# USB_Interface.net
KiCad netlist of a schematic drawn in Altium Designer
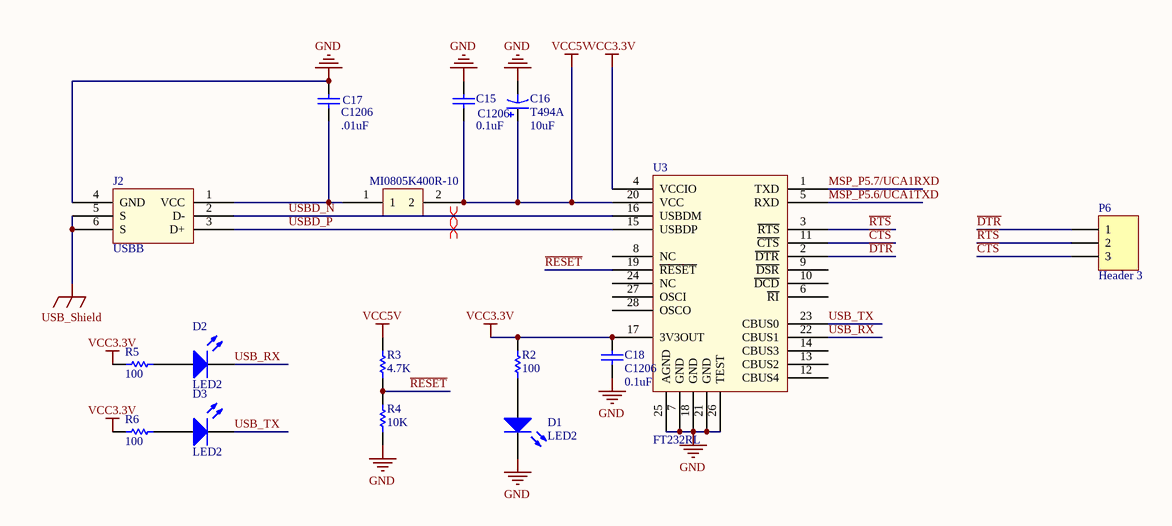
[diagram p0: USB Interface.SchDoc]

(export (version "E")
  (design (tool "Eeschema 10.0.6"))
  (components
    (comp (ref "C15")
      (value "C1206")
      (footprint "1206")
      (description "Ceramic Chip Capacitor - Standard")
      (fields (field (name "ALTIUM_VALUE") "0.1uF") (field (name "PUBLISHER") "Altium Limited"))
      (libsource (lib "KEMET Chip Capacitor") (part "C1206"))
    )
    (comp (ref "C16")
      (value "T494A")
      (footprint "A")
      (description "Solid Tantalum Chip Capacitor, Standard T494 Series - Low ESR, Industrial Grade")
      (fields (field (name "ALTIUM_VALUE") "10uF") (field (name "PUBLISHER") "Altium Limited"))
      (libsource (lib "KEMET Chip Capacitor") (part "T494A"))
    )
    (comp (ref "C17")
      (value "C1206")
      (footprint "1206")
      (description "Ceramic Chip Capacitor - Standard")
      (fields (field (name "ALTIUM_VALUE") ".01uF") (field (name "PUBLISHER") "Altium Limited"))
      (libsource (lib "KEMET Chip Capacitor") (part "C1206"))
    )
    (comp (ref "C18")
      (value "C1206")
      (footprint "1206")
      (description "Ceramic Chip Capacitor - Standard")
      (fields (field (name "ALTIUM_VALUE") "0.1uF") (field (name "PUBLISHER") "Altium Limited"))
      (libsource (lib "KEMET Chip Capacitor") (part "C1206"))
    )
    (comp (ref "D1")
      (value "LED2")
      (footprint "LED_LiteOn:LED_LiteOn_footprint")
      (description "Typical RED, GREEN, YELLOW, AMBER GaAs LED")
      (libsource (lib "Miscellaneous Devices") (part "LED2"))
    )
    (comp (ref "D2")
      (value "LED2")
      (footprint "LED_LiteOn:LED_LiteOn_footprint")
      (description "Typical RED, GREEN, YELLOW, AMBER GaAs LED")
      (libsource (lib "Miscellaneous Devices") (part "LED2"))
    )
    (comp (ref "D3")
      (value "LED2")
      (footprint "LED_LiteOn:LED_LiteOn_footprint")
      (description "Typical RED, GREEN, YELLOW, AMBER GaAs LED")
      (libsource (lib "Miscellaneous Devices") (part "LED2"))
    )
    (comp (ref "J2")
      (value "USBB")
      (footprint "usbb_pcb:PCBComponent_1")
      (libsource (lib "usbb_lib") (part "USBB"))
    )
    (comp (ref "P6")
      (value "Header 3")
      (footprint "HDR1X3")
      (description "Header, 3-Pin")
      (fields (field (name "PUBLISHER") "Altium Limited"))
      (libsource (lib "Miscellaneous Connectors") (part "Header 3"))
    )
    (comp (ref "R2")
      (value "100")
      (footprint "8-1206")
      (description "Thick Film Chip Resistor, 1 Ohm to 10M Ohm Range, 5% Tolerance, 1206 Size, 0.25 W")
      (fields (field (name "PUBLISHER") "Altium Limited"))
      (libsource (lib "Panasonic Resistor") (part "ERJ8GE"))
    )
    (comp (ref "R3")
      (value "4.7K")
      (footprint "8-1206")
      (description "Thick Film Chip Resistor, 1 Ohm to 10M Ohm Range, 5% Tolerance, 1206 Size, 0.25 W")
      (fields (field (name "PUBLISHER") "Altium Limited"))
      (libsource (lib "Panasonic Resistor") (part "ERJ8GE"))
    )
    (comp (ref "R4")
      (value "10K")
      (footprint "8-1206")
      (description "Thick Film Chip Resistor, 1 Ohm to 10M Ohm Range, 5% Tolerance, 1206 Size, 0.25 W")
      (fields (field (name "PUBLISHER") "Altium Limited"))
      (libsource (lib "Panasonic Resistor") (part "ERJ8GE"))
    )
    (comp (ref "R5")
      (value "100")
      (footprint "8-1206")
      (description "Thick Film Chip Resistor, 1 Ohm to 10M Ohm Range, 5% Tolerance, 1206 Size, 0.25 W")
      (fields (field (name "PUBLISHER") "Altium Limited"))
      (libsource (lib "Panasonic Resistor") (part "ERJ8GE"))
    )
    (comp (ref "R6")
      (value "100")
      (footprint "8-1206")
      (description "Thick Film Chip Resistor, 1 Ohm to 10M Ohm Range, 5% Tolerance, 1206 Size, 0.25 W")
      (fields (field (name "PUBLISHER") "Altium Limited"))
      (libsource (lib "Panasonic Resistor") (part "ERJ8GE"))
    )
    (comp (ref "U3")
      (value "FT232RL")
      (footprint "SOP65P780X200-28N")
      (libsource (lib "FT232RL") (part "FT232RL"))
    )
    (comp (ref "U4")
      (value "MI0805K400R-10")
      (footprint "INDC2012X11N")
      (description "ferrite bead")
      (libsource (lib "ferrite_bead") (part "ferrite bead"))
    )
  )
  (nets
    (net (code "1") (name "/MSP_P5.6{slash}UCA1TXD") (class "Default")
      (node (ref "U3") (pin "5") (pinfunction "RXD_5") (pintype "passive"))
    )
    (net (code "2") (name "/MSP_P5.7{slash}UCA1RXD") (class "Default")
      (node (ref "U3") (pin "1") (pinfunction "TXD_1") (pintype "passive"))
    )
    (net (code "3") (name "/USBD_N") (class "Default")
      (node (ref "J2") (pin "2") (pinfunction "D-_2") (pintype "passive"))
      (node (ref "U3") (pin "16") (pinfunction "USBDM_16") (pintype "passive"))
    )
    (net (code "4") (name "/USBD_P") (class "Default")
      (node (ref "J2") (pin "3") (pinfunction "D+_3") (pintype "passive"))
      (node (ref "U3") (pin "15") (pinfunction "USBDP_15") (pintype "passive"))
    )
    (net (code "5") (name "/USB_RX") (class "Default")
      (node (ref "D2") (pin "2") (pinfunction "K_2") (pintype "passive"))
      (node (ref "U3") (pin "22") (pinfunction "CBUS1_22") (pintype "passive"))
    )
    (net (code "6") (name "/USB_TX") (class "Default")
      (node (ref "D3") (pin "2") (pinfunction "K_2") (pintype "passive"))
      (node (ref "U3") (pin "23") (pinfunction "CBUS0_23") (pintype "passive"))
    )
    (net (code "7") (name "/~{CTS}") (class "Default")
      (node (ref "P6") (pin "3") (pinfunction "3_3") (pintype "passive"))
      (node (ref "U3") (pin "11") (pinfunction "~{CTS}_11") (pintype "passive"))
    )
    (net (code "8") (name "/~{DTR}") (class "Default")
      (node (ref "P6") (pin "1") (pinfunction "1_1") (pintype "passive"))
      (node (ref "U3") (pin "2") (pinfunction "~{DTR}_2") (pintype "passive"))
    )
    (net (code "9") (name "/~{RESET}") (class "Default")
      (node (ref "R3") (pin "2") (pinfunction "2_2") (pintype "passive"))
      (node (ref "R4") (pin "1") (pinfunction "1_1") (pintype "passive"))
      (node (ref "U3") (pin "19") (pinfunction "~{RESET}_19") (pintype "passive"))
    )
    (net (code "10") (name "/~{RTS}") (class "Default")
      (node (ref "P6") (pin "2") (pinfunction "2_2") (pintype "passive"))
      (node (ref "U3") (pin "3") (pinfunction "~{RTS}_3") (pintype "passive"))
    )
    (net (code "11") (name "GND") (class "Default")
      (node (ref "C15") (pin "2") (pinfunction "2_2") (pintype "passive"))
      (node (ref "C16") (pin "2") (pinfunction "2_2") (pintype "passive"))
      (node (ref "C17") (pin "1") (pinfunction "1_1") (pintype "passive"))
      (node (ref "C18") (pin "1") (pinfunction "1_1") (pintype "passive"))
      (node (ref "D1") (pin "2") (pinfunction "K_2") (pintype "passive"))
      (node (ref "J2") (pin "4") (pinfunction "GND_4") (pintype "power_in"))
      (node (ref "R4") (pin "2") (pinfunction "2_2") (pintype "passive"))
      (node (ref "U3") (pin "18") (pinfunction "GND_18") (pintype "power_in"))
      (node (ref "U3") (pin "21") (pinfunction "GND_21") (pintype "power_in"))
      (node (ref "U3") (pin "25") (pinfunction "AGND_25") (pintype "power_in"))
      (node (ref "U3") (pin "26") (pinfunction "TEST_26") (pintype "passive"))
      (node (ref "U3") (pin "7") (pinfunction "GND_7") (pintype "power_in"))
    )
    (net (code "12") (name "Net-(D1-A)") (class "Default")
      (node (ref "D1") (pin "1") (pinfunction "A_1") (pintype "passive"))
      (node (ref "R2") (pin "1") (pinfunction "1_1") (pintype "passive"))
    )
    (net (code "13") (name "Net-(D2-A)") (class "Default")
      (node (ref "D2") (pin "1") (pinfunction "A_1") (pintype "passive"))
      (node (ref "R5") (pin "2") (pinfunction "2_2") (pintype "passive"))
    )
    (net (code "14") (name "Net-(D3-A)") (class "Default")
      (node (ref "D3") (pin "1") (pinfunction "A_1") (pintype "passive"))
      (node (ref "R6") (pin "2") (pinfunction "2_2") (pintype "passive"))
    )
    (net (code "15") (name "Net-(J2-VCC)") (class "Default")
      (node (ref "C17") (pin "2") (pinfunction "2_2") (pintype "passive"))
      (node (ref "J2") (pin "1") (pinfunction "VCC_1") (pintype "power_in"))
      (node (ref "U4") (pin "1") (pinfunction "1_1") (pintype "passive"))
    )
    (net (code "16") (name "USB_Shield") (class "Default")
      (node (ref "J2") (pin "5") (pinfunction "S_5") (pintype "passive"))
      (node (ref "J2") (pin "6") (pinfunction "S_6") (pintype "passive"))
    )
    (net (code "17") (name "VCC3.3V") (class "Default")
      (node (ref "C18") (pin "2") (pinfunction "2_2") (pintype "passive"))
      (node (ref "R2") (pin "2") (pinfunction "2_2") (pintype "passive"))
      (node (ref "R5") (pin "1") (pinfunction "1_1") (pintype "passive"))
      (node (ref "R6") (pin "1") (pinfunction "1_1") (pintype "passive"))
      (node (ref "U3") (pin "17") (pinfunction "3V3OUT_17") (pintype "power_in"))
      (node (ref "U3") (pin "4") (pinfunction "VCCIO_4") (pintype "power_in"))
    )
    (net (code "18") (name "VCC5V") (class "Default")
      (node (ref "C15") (pin "1") (pinfunction "1_1") (pintype "passive"))
      (node (ref "C16") (pin "1") (pinfunction "1_1") (pintype "passive"))
      (node (ref "R3") (pin "1") (pinfunction "1_1") (pintype "passive"))
      (node (ref "U3") (pin "20") (pinfunction "VCC_20") (pintype "power_in"))
      (node (ref "U4") (pin "2") (pinfunction "2_2") (pintype "passive"))
    )
    (net (code "19") (name "unconnected-(U3-CBUS2-Pad13)") (class "Default")
      (node (ref "U3") (pin "13") (pinfunction "CBUS2_13") (pintype "passive"))
    )
    (net (code "20") (name "unconnected-(U3-CBUS3-Pad14)") (class "Default")
      (node (ref "U3") (pin "14") (pinfunction "CBUS3_14") (pintype "passive"))
    )
    (net (code "21") (name "unconnected-(U3-CBUS4-Pad12)") (class "Default")
      (node (ref "U3") (pin "12") (pinfunction "CBUS4_12") (pintype "passive"))
    )
    (net (code "22") (name "unconnected-(U3-NC-Pad8)") (class "Default")
      (node (ref "U3") (pin "8") (pinfunction "NC_8") (pintype "passive"))
    )
    (net (code "23") (name "unconnected-(U3-NC-Pad24)") (class "Default")
      (node (ref "U3") (pin "24") (pinfunction "NC_24") (pintype "passive"))
    )
    (net (code "24") (name "unconnected-(U3-OSCI-Pad27)") (class "Default")
      (node (ref "U3") (pin "27") (pinfunction "OSCI_27") (pintype "passive"))
    )
    (net (code "25") (name "unconnected-(U3-OSCO-Pad28)") (class "Default")
      (node (ref "U3") (pin "28") (pinfunction "OSCO_28") (pintype "passive"))
    )
    (net (code "26") (name "unconnected-(U3-~{DCD}-Pad10)") (class "Default")
      (node (ref "U3") (pin "10") (pinfunction "~{DCD}_10") (pintype "passive"))
    )
    (net (code "27") (name "unconnected-(U3-~{DSR}-Pad9)") (class "Default")
      (node (ref "U3") (pin "9") (pinfunction "~{DSR}_9") (pintype "passive"))
    )
    (net (code "28") (name "unconnected-(U3-~{RI}-Pad6)") (class "Default")
      (node (ref "U3") (pin "6") (pinfunction "~{RI}_6") (pintype "passive"))
    )
  )
)
